# 6in1.net
KiCad netlist of a schematic drawn in EAGLE
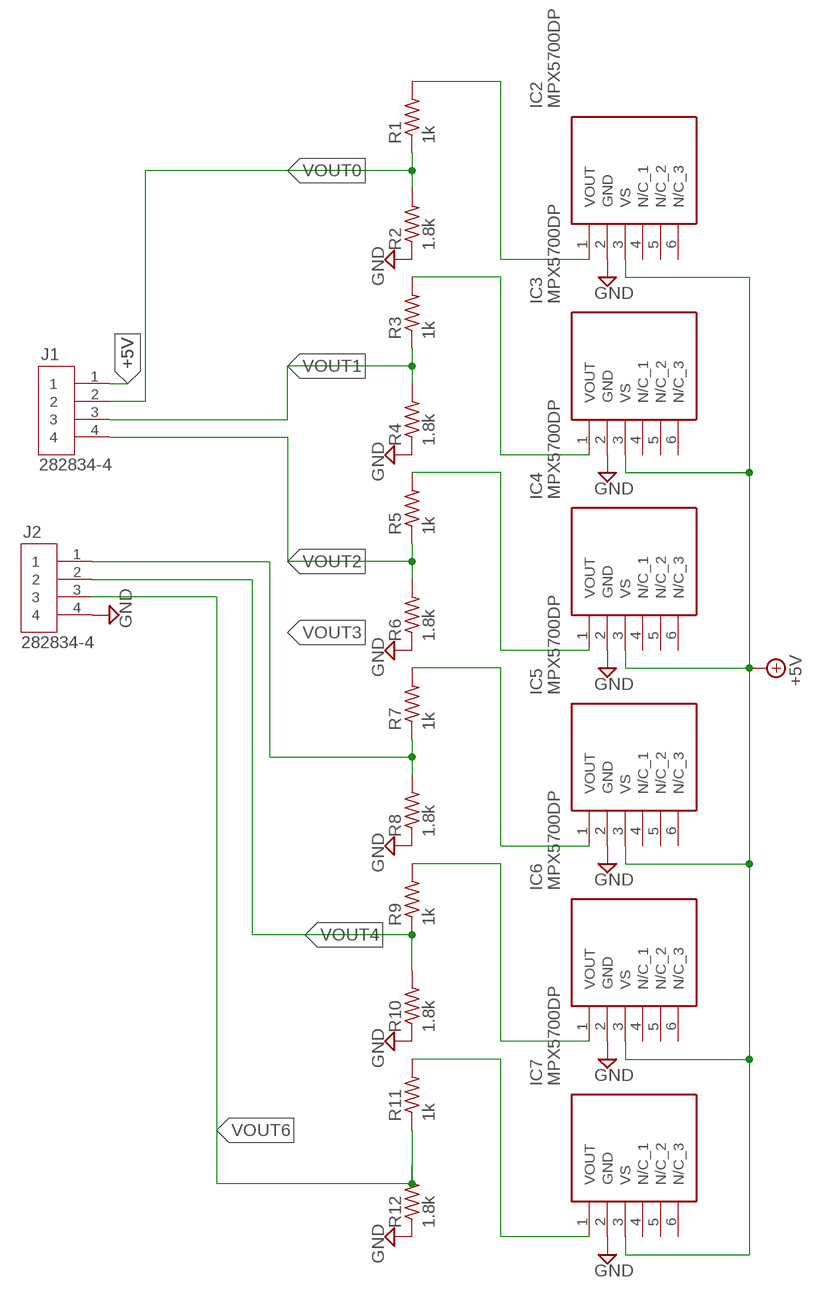
[diagram p0: schematic, sheet 1]

(export (version "E")
  (design (tool "Eeschema 10.0.6"))
  (components
    (comp (ref "IC2")
      (value "MPX5700DP")
      (footprint "eagle-import:MPX5700DP")
      (libsource (lib "eagle-import") (part "MPX5700DP"))
    )
    (comp (ref "IC3")
      (value "MPX5700DP")
      (footprint "eagle-import:MPX5700DP")
      (libsource (lib "eagle-import") (part "MPX5700DP"))
    )
    (comp (ref "IC4")
      (value "MPX5700DP")
      (footprint "eagle-import:MPX5700DP")
      (libsource (lib "eagle-import") (part "MPX5700DP"))
    )
    (comp (ref "IC5")
      (value "MPX5700DP")
      (footprint "eagle-import:MPX5700DP")
      (libsource (lib "eagle-import") (part "MPX5700DP"))
    )
    (comp (ref "IC6")
      (value "MPX5700DP")
      (footprint "eagle-import:MPX5700DP")
      (libsource (lib "eagle-import") (part "MPX5700DP"))
    )
    (comp (ref "IC7")
      (value "MPX5700DP")
      (footprint "eagle-import:MPX5700DP")
      (libsource (lib "eagle-import") (part "MPX5700DP"))
    )
    (comp (ref "J1")
      (value "282834-4")
      (footprint "eagle-import:HDRV4W85P254_4X1_1062X650X1000")
      (fields (field (name "MF") "TE Connectivity"))
      (libsource (lib "eagle-import") (part "282834-4"))
    )
    (comp (ref "J2")
      (value "282834-4")
      (footprint "eagle-import:HDRV4W85P254_4X1_1062X650X1000")
      (fields (field (name "MF") "TE Connectivity"))
      (libsource (lib "eagle-import") (part "282834-4"))
    )
    (comp (ref "R1")
      (value "1k")
      (footprint "eagle-import:0204V")
      (libsource (lib "eagle-import") (part "R-US_0204/2V"))
    )
    (comp (ref "R2")
      (value "1.8k")
      (footprint "eagle-import:0204V")
      (libsource (lib "eagle-import") (part "R-US_0204/2V"))
    )
    (comp (ref "R3")
      (value "1k")
      (footprint "eagle-import:0204V")
      (libsource (lib "eagle-import") (part "R-US_0204/2V"))
    )
    (comp (ref "R4")
      (value "1.8k")
      (footprint "eagle-import:0204V")
      (libsource (lib "eagle-import") (part "R-US_0204/2V"))
    )
    (comp (ref "R5")
      (value "1k")
      (footprint "eagle-import:0204V")
      (libsource (lib "eagle-import") (part "R-US_0204/2V"))
    )
    (comp (ref "R6")
      (value "1.8k")
      (footprint "eagle-import:0204V")
      (libsource (lib "eagle-import") (part "R-US_0204/2V"))
    )
    (comp (ref "R7")
      (value "1k")
      (footprint "eagle-import:0204V")
      (libsource (lib "eagle-import") (part "R-US_0204/2V"))
    )
    (comp (ref "R8")
      (value "1.8k")
      (footprint "eagle-import:0204V")
      (libsource (lib "eagle-import") (part "R-US_0204/2V"))
    )
    (comp (ref "R9")
      (value "1k")
      (footprint "eagle-import:0204V")
      (libsource (lib "eagle-import") (part "R-US_0204/2V"))
    )
    (comp (ref "R10")
      (value "1.8k")
      (footprint "eagle-import:0204V")
      (libsource (lib "eagle-import") (part "R-US_0204/2V"))
    )
    (comp (ref "R11")
      (value "1k")
      (footprint "eagle-import:0204V")
      (libsource (lib "eagle-import") (part "R-US_0204/2V"))
    )
    (comp (ref "R12")
      (value "1.8k")
      (footprint "eagle-import:0204V")
      (libsource (lib "eagle-import") (part "R-US_0204/2V"))
    )
  )
  (nets
    (net (code "1") (name "+5V") (class "Default")
      (node (ref "IC2") (pin "3") (pinfunction "VS_3") (pintype "bidirectional"))
      (node (ref "IC3") (pin "3") (pinfunction "VS_3") (pintype "bidirectional"))
      (node (ref "IC4") (pin "3") (pinfunction "VS_3") (pintype "bidirectional"))
      (node (ref "IC5") (pin "3") (pinfunction "VS_3") (pintype "bidirectional"))
      (node (ref "IC6") (pin "3") (pinfunction "VS_3") (pintype "bidirectional"))
      (node (ref "IC7") (pin "3") (pinfunction "VS_3") (pintype "bidirectional"))
      (node (ref "J1") (pin "1") (pinfunction "1_1") (pintype "passive"))
    )
    (net (code "2") (name "GND") (class "Default")
      (node (ref "IC2") (pin "2") (pinfunction "GND_2") (pintype "bidirectional"))
      (node (ref "IC3") (pin "2") (pinfunction "GND_2") (pintype "bidirectional"))
      (node (ref "IC4") (pin "2") (pinfunction "GND_2") (pintype "bidirectional"))
      (node (ref "IC5") (pin "2") (pinfunction "GND_2") (pintype "bidirectional"))
      (node (ref "IC6") (pin "2") (pinfunction "GND_2") (pintype "bidirectional"))
      (node (ref "IC7") (pin "2") (pinfunction "GND_2") (pintype "bidirectional"))
      (node (ref "J2") (pin "4") (pinfunction "4_4") (pintype "passive"))
      (node (ref "R10") (pin "1") (pinfunction "1_1") (pintype "passive"))
      (node (ref "R12") (pin "1") (pinfunction "1_1") (pintype "passive"))
      (node (ref "R2") (pin "1") (pinfunction "1_1") (pintype "passive"))
      (node (ref "R4") (pin "1") (pinfunction "1_1") (pintype "passive"))
      (node (ref "R6") (pin "1") (pinfunction "1_1") (pintype "passive"))
      (node (ref "R8") (pin "1") (pinfunction "1_1") (pintype "passive"))
    )
    (net (code "3") (name "Net-(IC2-VOUT)") (class "Default")
      (node (ref "IC2") (pin "1") (pinfunction "VOUT_1") (pintype "bidirectional"))
      (node (ref "R1") (pin "2") (pinfunction "2_2") (pintype "passive"))
    )
    (net (code "4") (name "Net-(IC3-VOUT)") (class "Default")
      (node (ref "IC3") (pin "1") (pinfunction "VOUT_1") (pintype "bidirectional"))
      (node (ref "R3") (pin "2") (pinfunction "2_2") (pintype "passive"))
    )
    (net (code "5") (name "Net-(IC4-VOUT)") (class "Default")
      (node (ref "IC4") (pin "1") (pinfunction "VOUT_1") (pintype "bidirectional"))
      (node (ref "R5") (pin "2") (pinfunction "2_2") (pintype "passive"))
    )
    (net (code "6") (name "Net-(IC5-VOUT)") (class "Default")
      (node (ref "IC5") (pin "1") (pinfunction "VOUT_1") (pintype "bidirectional"))
      (node (ref "R7") (pin "2") (pinfunction "2_2") (pintype "passive"))
    )
    (net (code "7") (name "Net-(IC6-VOUT)") (class "Default")
      (node (ref "IC6") (pin "1") (pinfunction "VOUT_1") (pintype "bidirectional"))
      (node (ref "R9") (pin "2") (pinfunction "2_2") (pintype "passive"))
    )
    (net (code "8") (name "Net-(IC7-VOUT)") (class "Default")
      (node (ref "IC7") (pin "1") (pinfunction "VOUT_1") (pintype "bidirectional"))
      (node (ref "R11") (pin "2") (pinfunction "2_2") (pintype "passive"))
    )
    (net (code "9") (name "VOUT0") (class "Default")
      (node (ref "J1") (pin "2") (pinfunction "2_2") (pintype "passive"))
      (node (ref "R1") (pin "1") (pinfunction "1_1") (pintype "passive"))
      (node (ref "R2") (pin "2") (pinfunction "2_2") (pintype "passive"))
    )
    (net (code "10") (name "VOUT1") (class "Default")
      (node (ref "J1") (pin "3") (pinfunction "3_3") (pintype "passive"))
      (node (ref "R3") (pin "1") (pinfunction "1_1") (pintype "passive"))
      (node (ref "R4") (pin "2") (pinfunction "2_2") (pintype "passive"))
    )
    (net (code "11") (name "VOUT2") (class "Default")
      (node (ref "J1") (pin "4") (pinfunction "4_4") (pintype "passive"))
      (node (ref "R5") (pin "1") (pinfunction "1_1") (pintype "passive"))
      (node (ref "R6") (pin "2") (pinfunction "2_2") (pintype "passive"))
    )
    (net (code "12") (name "VOUT3") (class "Default")
      (node (ref "J2") (pin "1") (pinfunction "1_1") (pintype "passive"))
      (node (ref "R7") (pin "1") (pinfunction "1_1") (pintype "passive"))
      (node (ref "R8") (pin "2") (pinfunction "2_2") (pintype "passive"))
    )
    (net (code "13") (name "VOUT4") (class "Default")
      (node (ref "J2") (pin "2") (pinfunction "2_2") (pintype "passive"))
      (node (ref "R10") (pin "2") (pinfunction "2_2") (pintype "passive"))
      (node (ref "R9") (pin "1") (pinfunction "1_1") (pintype "passive"))
    )
    (net (code "14") (name "VOUT6") (class "Default")
      (node (ref "J2") (pin "3") (pinfunction "3_3") (pintype "passive"))
      (node (ref "R11") (pin "1") (pinfunction "1_1") (pintype "passive"))
      (node (ref "R12") (pin "2") (pinfunction "2_2") (pintype "passive"))
    )
    (net (code "15") (name "unconnected-(IC2-N{slash}C_1-Pad4)") (class "Default")
      (node (ref "IC2") (pin "4") (pinfunction "N/C_1_4") (pintype "bidirectional"))
    )
    (net (code "16") (name "unconnected-(IC2-N{slash}C_2-Pad5)") (class "Default")
      (node (ref "IC2") (pin "5") (pinfunction "N/C_2_5") (pintype "bidirectional"))
    )
    (net (code "17") (name "unconnected-(IC2-N{slash}C_3-Pad6)") (class "Default")
      (node (ref "IC2") (pin "6") (pinfunction "N/C_3_6") (pintype "bidirectional"))
    )
    (net (code "18") (name "unconnected-(IC3-N{slash}C_1-Pad4)") (class "Default")
      (node (ref "IC3") (pin "4") (pinfunction "N/C_1_4") (pintype "bidirectional"))
    )
    (net (code "19") (name "unconnected-(IC3-N{slash}C_2-Pad5)") (class "Default")
      (node (ref "IC3") (pin "5") (pinfunction "N/C_2_5") (pintype "bidirectional"))
    )
    (net (code "20") (name "unconnected-(IC3-N{slash}C_3-Pad6)") (class "Default")
      (node (ref "IC3") (pin "6") (pinfunction "N/C_3_6") (pintype "bidirectional"))
    )
    (net (code "21") (name "unconnected-(IC4-N{slash}C_1-Pad4)") (class "Default")
      (node (ref "IC4") (pin "4") (pinfunction "N/C_1_4") (pintype "bidirectional"))
    )
    (net (code "22") (name "unconnected-(IC4-N{slash}C_2-Pad5)") (class "Default")
      (node (ref "IC4") (pin "5") (pinfunction "N/C_2_5") (pintype "bidirectional"))
    )
    (net (code "23") (name "unconnected-(IC4-N{slash}C_3-Pad6)") (class "Default")
      (node (ref "IC4") (pin "6") (pinfunction "N/C_3_6") (pintype "bidirectional"))
    )
    (net (code "24") (name "unconnected-(IC5-N{slash}C_1-Pad4)") (class "Default")
      (node (ref "IC5") (pin "4") (pinfunction "N/C_1_4") (pintype "bidirectional"))
    )
    (net (code "25") (name "unconnected-(IC5-N{slash}C_2-Pad5)") (class "Default")
      (node (ref "IC5") (pin "5") (pinfunction "N/C_2_5") (pintype "bidirectional"))
    )
    (net (code "26") (name "unconnected-(IC5-N{slash}C_3-Pad6)") (class "Default")
      (node (ref "IC5") (pin "6") (pinfunction "N/C_3_6") (pintype "bidirectional"))
    )
    (net (code "27") (name "unconnected-(IC6-N{slash}C_1-Pad4)") (class "Default")
      (node (ref "IC6") (pin "4") (pinfunction "N/C_1_4") (pintype "bidirectional"))
    )
    (net (code "28") (name "unconnected-(IC6-N{slash}C_2-Pad5)") (class "Default")
      (node (ref "IC6") (pin "5") (pinfunction "N/C_2_5") (pintype "bidirectional"))
    )
    (net (code "29") (name "unconnected-(IC6-N{slash}C_3-Pad6)") (class "Default")
      (node (ref "IC6") (pin "6") (pinfunction "N/C_3_6") (pintype "bidirectional"))
    )
    (net (code "30") (name "unconnected-(IC7-N{slash}C_1-Pad4)") (class "Default")
      (node (ref "IC7") (pin "4") (pinfunction "N/C_1_4") (pintype "bidirectional"))
    )
    (net (code "31") (name "unconnected-(IC7-N{slash}C_2-Pad5)") (class "Default")
      (node (ref "IC7") (pin "5") (pinfunction "N/C_2_5") (pintype "bidirectional"))
    )
    (net (code "32") (name "unconnected-(IC7-N{slash}C_3-Pad6)") (class "Default")
      (node (ref "IC7") (pin "6") (pinfunction "N/C_3_6") (pintype "bidirectional"))
    )
  )
)
